# ir_amplifier.net
KiCad netlist of a schematic drawn in EAGLE
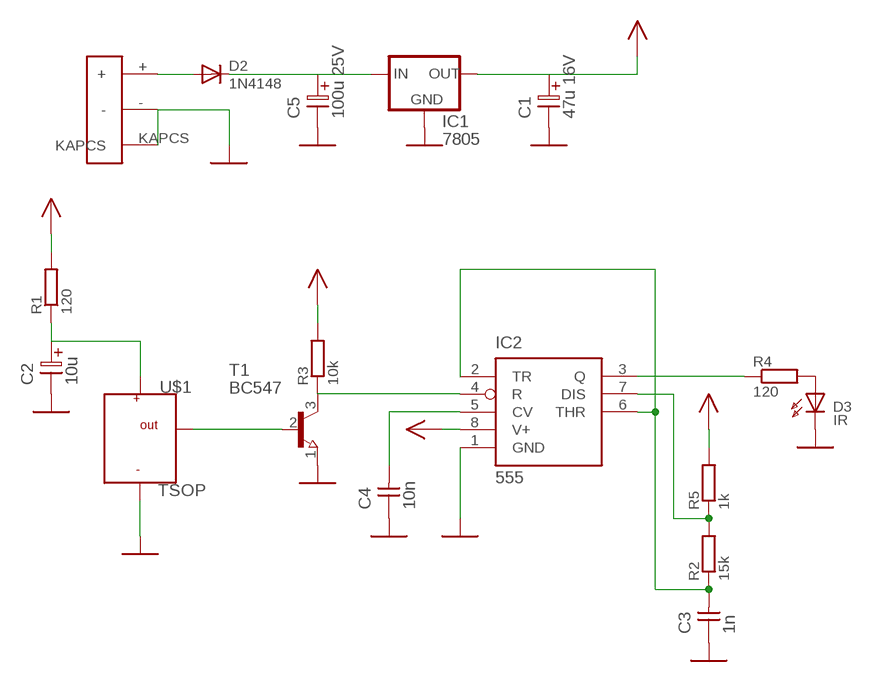
[diagram p0: schematic, sheet 1]

(export (version "E")
  (design (tool "Eeschema 10.0.6"))
  (components
    (comp (ref "C1")
      (value "47u 16V")
      (footprint "eagle-import:ES-2,5L")
      (libsource (lib "eagle-import") (part "ELC-2,5L"))
    )
    (comp (ref "C2")
      (value "10u")
      (footprint "eagle-import:ES-2,5L")
      (libsource (lib "eagle-import") (part "ELC-2,5L"))
    )
    (comp (ref "C3")
      (value "1n")
      (footprint "eagle-import:C-5")
      (libsource (lib "eagle-import") (part "CAPNP-5"))
    )
    (comp (ref "C4")
      (value "10n")
      (footprint "eagle-import:C-5")
      (libsource (lib "eagle-import") (part "CAPNP-5"))
    )
    (comp (ref "C5")
      (value "100u 25V")
      (footprint "eagle-import:ES-5")
      (libsource (lib "eagle-import") (part "ELC-5"))
    )
    (comp (ref "D2")
      (value "1N4148")
      (footprint "eagle-import:DO35-10")
      (libsource (lib "eagle-import") (part "1N4148"))
    )
    (comp (ref "D3")
      (value "IR")
      (footprint "eagle-import:LED5")
      (libsource (lib "eagle-import") (part "LED5"))
    )
    (comp (ref "IC1")
      (value "7805")
      (footprint "eagle-import:78XXS")
      (libsource (lib "eagle-import") (part "78XXS"))
    )
    (comp (ref "IC2")
      (value "555")
      (footprint "eagle-import:DIL8")
      (libsource (lib "eagle-import") (part "555"))
    )
    (comp (ref "R1")
      (value "120")
      (footprint "eagle-import:0207_10")
      (libsource (lib "eagle-import") (part "0207/10"))
    )
    (comp (ref "R2")
      (value "15k")
      (footprint "eagle-import:0207_10")
      (libsource (lib "eagle-import") (part "0207/10"))
    )
    (comp (ref "R3")
      (value "10k")
      (footprint "eagle-import:0207_10")
      (libsource (lib "eagle-import") (part "0207/10"))
    )
    (comp (ref "R4")
      (value "120")
      (footprint "eagle-import:0207_10")
      (libsource (lib "eagle-import") (part "0207/10"))
    )
    (comp (ref "R5")
      (value "1k")
      (footprint "eagle-import:0207_10")
      (libsource (lib "eagle-import") (part "0207/10"))
    )
    (comp (ref "T1")
      (value "BC547")
      (footprint "eagle-import:TO92")
      (libsource (lib "eagle-import") (part "BC547"))
    )
    (comp (ref "U$1")
      (value "TSOP")
      (footprint "eagle-import:TSOP")
      (libsource (lib "eagle-import") (part "TSOP"))
    )
    (comp (ref "U$2")
      (value "DC ALJ")
      (footprint "eagle-import:DC_ALJ")
      (libsource (lib "eagle-import") (part "DC_ALJ"))
    )
  )
  (nets
    (net (code "1") (name "GND") (class "Default")
      (node (ref "C1") (pin "2") (pinfunction "2_2") (pintype "passive"))
      (node (ref "C2") (pin "2") (pinfunction "2_2") (pintype "passive"))
      (node (ref "C3") (pin "1") (pinfunction "1_1") (pintype "passive"))
      (node (ref "C4") (pin "1") (pinfunction "1_1") (pintype "passive"))
      (node (ref "C5") (pin "2") (pinfunction "2_2") (pintype "passive"))
      (node (ref "D3") (pin "K") (pinfunction "K_K") (pintype "passive"))
      (node (ref "IC1") (pin "GND") (pinfunction "GND_GND") (pintype "input"))
      (node (ref "IC2") (pin "1") (pinfunction "GND_1") (pintype "power_in"))
      (node (ref "T1") (pin "1") (pinfunction "E_1") (pintype "passive"))
      (node (ref "U$1") (pin "-") (pinfunction "-_-") (pintype "passive"))
      (node (ref "U$2") (pin "-") (pinfunction "-_-") (pintype "bidirectional"))
      (node (ref "U$2") (pin "KAPCS") (pinfunction "KAPCS_KAPCS") (pintype "bidirectional"))
    )
    (net (code "2") (name "Net-(C2-Pad1)") (class "Default")
      (node (ref "C2") (pin "1") (pinfunction "1_1") (pintype "passive"))
      (node (ref "R1") (pin "1") (pinfunction "1_1") (pintype "passive"))
      (node (ref "U$1") (pin "+") (pinfunction "+_+") (pintype "passive"))
    )
    (net (code "3") (name "Net-(C5-Pad1)") (class "Default")
      (node (ref "C5") (pin "1") (pinfunction "1_1") (pintype "passive"))
      (node (ref "D2") (pin "K") (pinfunction "K_K") (pintype "passive"))
      (node (ref "IC1") (pin "IN") (pinfunction "IN_IN") (pintype "input"))
    )
    (net (code "4") (name "Net-(D2-PadA)") (class "Default")
      (node (ref "D2") (pin "A") (pinfunction "A_A") (pintype "passive"))
      (node (ref "U$2") (pin "+") (pinfunction "+_+") (pintype "bidirectional"))
    )
    (net (code "5") (name "Net-(D3-PadA)") (class "Default")
      (node (ref "D3") (pin "A") (pinfunction "A_A") (pintype "passive"))
      (node (ref "R4") (pin "2") (pinfunction "2_2") (pintype "passive"))
    )
    (net (code "6") (name "Net-(IC2-CV)") (class "Default")
      (node (ref "C4") (pin "2") (pinfunction "2_2") (pintype "passive"))
      (node (ref "IC2") (pin "5") (pinfunction "CV_5") (pintype "input"))
    )
    (net (code "7") (name "Net-(IC2-DIS)") (class "Default")
      (node (ref "IC2") (pin "7") (pinfunction "DIS_7") (pintype "input"))
      (node (ref "R2") (pin "2") (pinfunction "2_2") (pintype "passive"))
      (node (ref "R5") (pin "1") (pinfunction "1_1") (pintype "passive"))
    )
    (net (code "8") (name "Net-(IC2-Q)") (class "Default")
      (node (ref "IC2") (pin "3") (pinfunction "Q_3") (pintype "output"))
      (node (ref "R4") (pin "1") (pinfunction "1_1") (pintype "passive"))
    )
    (net (code "9") (name "Net-(IC2-R)") (class "Default")
      (node (ref "IC2") (pin "4") (pinfunction "R_4") (pintype "input"))
      (node (ref "R3") (pin "1") (pinfunction "1_1") (pintype "passive"))
      (node (ref "T1") (pin "3") (pinfunction "C_3") (pintype "passive"))
    )
    (net (code "10") (name "Net-(IC2-THR)") (class "Default")
      (node (ref "C3") (pin "2") (pinfunction "2_2") (pintype "passive"))
      (node (ref "IC2") (pin "2") (pinfunction "TR_2") (pintype "input"))
      (node (ref "IC2") (pin "6") (pinfunction "THR_6") (pintype "input"))
      (node (ref "R2") (pin "1") (pinfunction "1_1") (pintype "passive"))
    )
    (net (code "11") (name "Net-(T1-B)") (class "Default")
      (node (ref "T1") (pin "2") (pinfunction "B_2") (pintype "passive"))
      (node (ref "U$1") (pin "OUT") (pinfunction "OUT_OUT") (pintype "passive"))
    )
    (net (code "12") (name "VCC") (class "Default")
      (node (ref "C1") (pin "1") (pinfunction "1_1") (pintype "passive"))
      (node (ref "IC1") (pin "OUT") (pinfunction "OUT_OUT") (pintype "passive"))
      (node (ref "IC2") (pin "8") (pinfunction "V+_8") (pintype "power_in"))
      (node (ref "R1") (pin "2") (pinfunction "2_2") (pintype "passive"))
      (node (ref "R3") (pin "2") (pinfunction "2_2") (pintype "passive"))
      (node (ref "R5") (pin "2") (pinfunction "2_2") (pintype "passive"))
    )
  )
)
